# GR_Barillet.net
KiCad netlist of a schematic drawn in Altium Designer
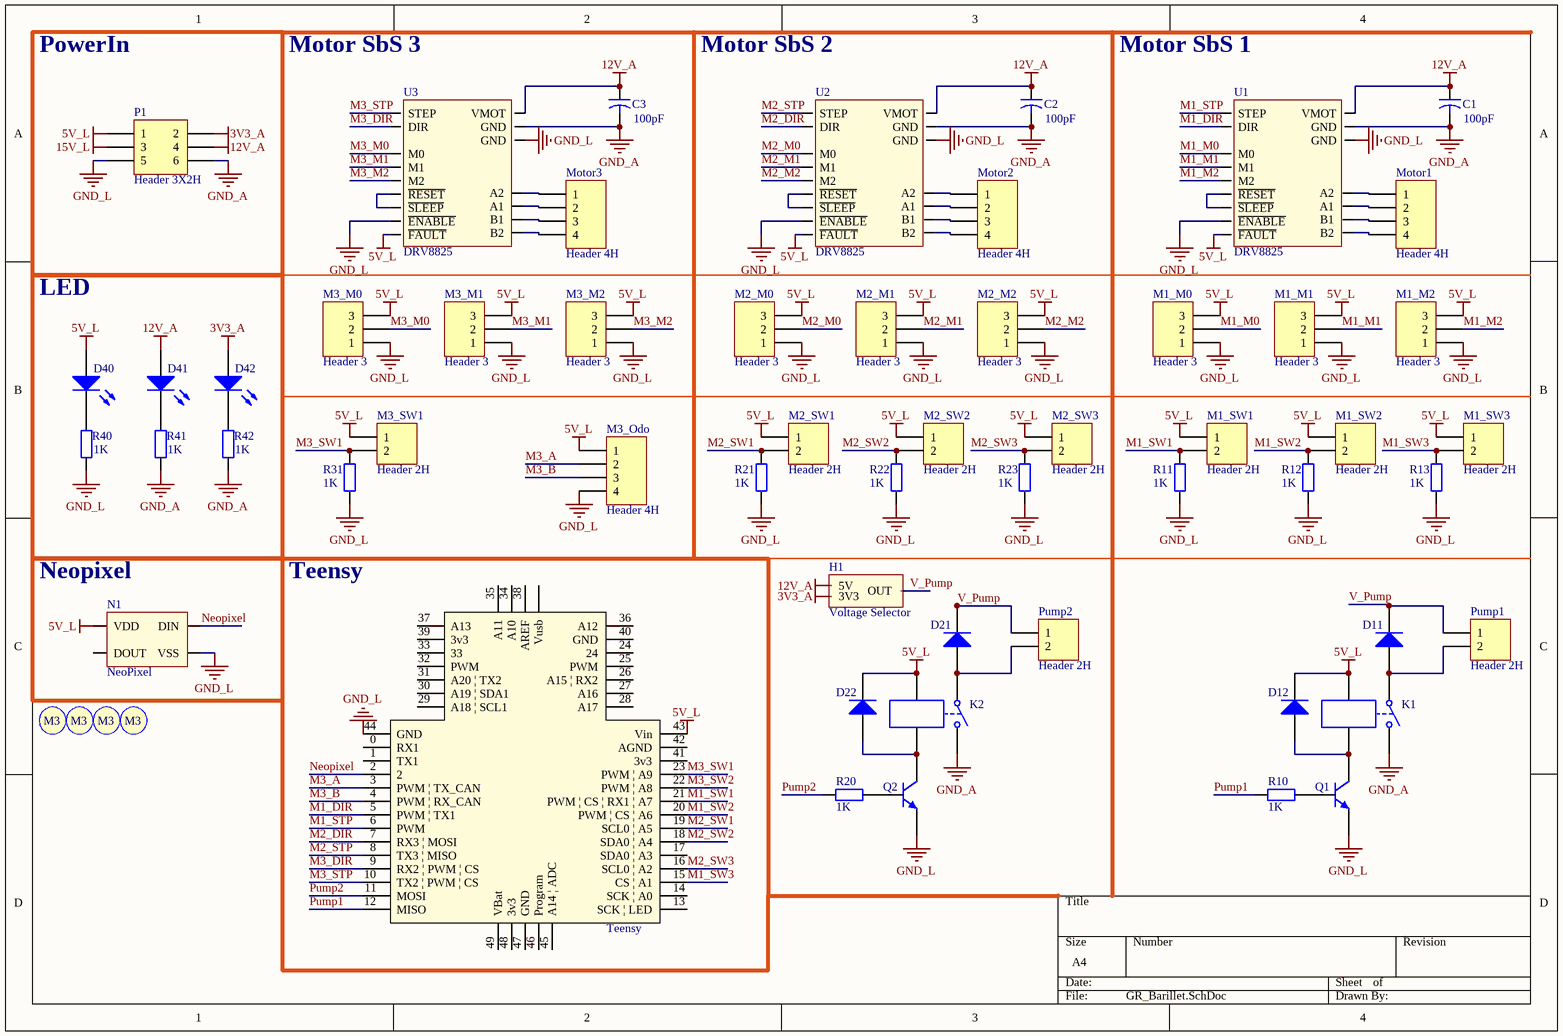
[diagram p0: GR_Barillet.SchDoc]

(export (version "E")
  (design (tool "Eeschema 10.0.6"))
  (components
    (comp (ref "C1")
      (value "100pF")
      (footprint "Condensateur")
      (description "Capacitor")
      (fields (field (name "Comment") "Cap2") (field (name "PUBLISHER") "Altium Limited"))
      (libsource (lib "Miscellaneous Devices") (part "Cap2"))
    )
    (comp (ref "C2")
      (value "100pF")
      (footprint "Condensateur")
      (description "Capacitor")
      (fields (field (name "Comment") "Cap2") (field (name "PUBLISHER") "Altium Limited"))
      (libsource (lib "Miscellaneous Devices") (part "Cap2"))
    )
    (comp (ref "C3")
      (value "100pF")
      (footprint "Condensateur")
      (description "Capacitor")
      (fields (field (name "Comment") "Cap2") (field (name "PUBLISHER") "Altium Limited"))
      (libsource (lib "Miscellaneous Devices") (part "Cap2"))
    )
    (comp (ref "D11")
      (value "Diode")
      (footprint "AXIAL-0.3")
      (description "Default Diode")
      (fields (field (name "PUBLISHER") "Altium Limited"))
      (libsource (lib "Miscellaneous Devices") (part "Diode"))
    )
    (comp (ref "D12")
      (value "Diode")
      (footprint "3.2X1.6X1.1")
      (description "Default Diode")
      (fields (field (name "PUBLISHER") "Altium Limited"))
      (libsource (lib "Miscellaneous Devices") (part "Diode"))
    )
    (comp (ref "D21")
      (value "Diode")
      (footprint "AXIAL-0.3")
      (description "Default Diode")
      (fields (field (name "PUBLISHER") "Altium Limited"))
      (libsource (lib "Miscellaneous Devices") (part "Diode"))
    )
    (comp (ref "D22")
      (value "Diode")
      (footprint "3.2X1.6X1.1")
      (description "Default Diode")
      (fields (field (name "PUBLISHER") "Altium Limited"))
      (libsource (lib "Miscellaneous Devices") (part "Diode"))
    )
    (comp (ref "D40")
      (value "LED0")
      (footprint "3.2X1.6X1.1")
      (description "Typical INFRARED GaAs LED")
      (fields (field (name "PUBLISHER") "Altium Limited"))
      (libsource (lib "Miscellaneous Devices") (part "LED0"))
    )
    (comp (ref "D41")
      (value "LED0")
      (footprint "3.2X1.6X1.1")
      (description "Typical INFRARED GaAs LED")
      (fields (field (name "PUBLISHER") "Altium Limited"))
      (libsource (lib "Miscellaneous Devices") (part "LED0"))
    )
    (comp (ref "D42")
      (value "LED0")
      (footprint "3.2X1.6X1.1")
      (description "Typical INFRARED GaAs LED")
      (fields (field (name "PUBLISHER") "Altium Limited"))
      (libsource (lib "Miscellaneous Devices") (part "LED0"))
    )
    (comp (ref "H1")
      (value "Voltage Selector")
      (footprint "Robot_2019:VOLTAGE SELECTOR")
      (description "Selection of voltage by soldering pads")
      (libsource (lib "Robot_2019") (part "Voltage Selector"))
    )
    (comp (ref "K1")
      (value "Relay-SPST")
      (footprint "Relay")
      (description "Single-Pole Single-Throw Relay")
      (fields (field (name "PUBLISHER") "Altium Limited"))
      (libsource (lib "Miscellaneous Devices") (part "Relay-SPST"))
    )
    (comp (ref "K2")
      (value "Relay-SPST")
      (footprint "Relay")
      (description "Single-Pole Single-Throw Relay")
      (fields (field (name "PUBLISHER") "Altium Limited"))
      (libsource (lib "Miscellaneous Devices") (part "Relay-SPST"))
    )
    (comp (ref "M1_M0")
      (value "Header 3")
      (footprint "HDR1X3")
      (description "Header, 3-Pin")
      (fields (field (name "PUBLISHER") "Altium Limited"))
      (libsource (lib "Miscellaneous Connectors") (part "Header 3"))
    )
    (comp (ref "M1_M1")
      (value "Header 3")
      (footprint "HDR1X3")
      (description "Header, 3-Pin")
      (fields (field (name "PUBLISHER") "Altium Limited"))
      (libsource (lib "Miscellaneous Connectors") (part "Header 3"))
    )
    (comp (ref "M1_M2")
      (value "Header 3")
      (footprint "HDR1X3")
      (description "Header, 3-Pin")
      (fields (field (name "PUBLISHER") "Altium Limited"))
      (libsource (lib "Miscellaneous Connectors") (part "Header 3"))
    )
    (comp (ref "M1_SW1")
      (value "Header 2H")
      (footprint "Molex SPOX 2x1H")
      (description "Header, 2-Pin, Right Angle")
      (fields (field (name "PUBLISHER") "Altium Limited"))
      (libsource (lib "Miscellaneous Connectors") (part "Header 2H"))
    )
    (comp (ref "M1_SW2")
      (value "Header 2H")
      (footprint "Molex SPOX 2x1H")
      (description "Header, 2-Pin, Right Angle")
      (fields (field (name "PUBLISHER") "Altium Limited"))
      (libsource (lib "Miscellaneous Connectors") (part "Header 2H"))
    )
    (comp (ref "M1_SW3")
      (value "Header 2H")
      (footprint "Molex SPOX 2x1H")
      (description "Header, 2-Pin, Right Angle")
      (fields (field (name "PUBLISHER") "Altium Limited"))
      (libsource (lib "Miscellaneous Connectors") (part "Header 2H"))
    )
    (comp (ref "M2_M0")
      (value "Header 3")
      (footprint "HDR1X3")
      (description "Header, 3-Pin")
      (fields (field (name "PUBLISHER") "Altium Limited"))
      (libsource (lib "Miscellaneous Connectors") (part "Header 3"))
    )
    (comp (ref "M2_M1")
      (value "Header 3")
      (footprint "HDR1X3")
      (description "Header, 3-Pin")
      (fields (field (name "PUBLISHER") "Altium Limited"))
      (libsource (lib "Miscellaneous Connectors") (part "Header 3"))
    )
    (comp (ref "M2_M2")
      (value "Header 3")
      (footprint "HDR1X3")
      (description "Header, 3-Pin")
      (fields (field (name "PUBLISHER") "Altium Limited"))
      (libsource (lib "Miscellaneous Connectors") (part "Header 3"))
    )
    (comp (ref "M2_SW1")
      (value "Header 2H")
      (footprint "Molex SPOX 2x1H")
      (description "Header, 2-Pin, Right Angle")
      (fields (field (name "PUBLISHER") "Altium Limited"))
      (libsource (lib "Miscellaneous Connectors") (part "Header 2H"))
    )
    (comp (ref "M2_SW2")
      (value "Header 2H")
      (footprint "Molex SPOX 2x1H")
      (description "Header, 2-Pin, Right Angle")
      (fields (field (name "PUBLISHER") "Altium Limited"))
      (libsource (lib "Miscellaneous Connectors") (part "Header 2H"))
    )
    (comp (ref "M2_SW3")
      (value "Header 2H")
      (footprint "Molex SPOX 2x1H")
      (description "Header, 2-Pin, Right Angle")
      (fields (field (name "PUBLISHER") "Altium Limited"))
      (libsource (lib "Miscellaneous Connectors") (part "Header 2H"))
    )
    (comp (ref "M3_M0")
      (value "Header 3")
      (footprint "HDR1X3")
      (description "Header, 3-Pin")
      (fields (field (name "PUBLISHER") "Altium Limited"))
      (libsource (lib "Miscellaneous Connectors") (part "Header 3"))
    )
    (comp (ref "M3_M1")
      (value "Header 3")
      (footprint "HDR1X3")
      (description "Header, 3-Pin")
      (fields (field (name "PUBLISHER") "Altium Limited"))
      (libsource (lib "Miscellaneous Connectors") (part "Header 3"))
    )
    (comp (ref "M3_M2")
      (value "Header 3")
      (footprint "HDR1X3")
      (description "Header, 3-Pin")
      (fields (field (name "PUBLISHER") "Altium Limited"))
      (libsource (lib "Miscellaneous Connectors") (part "Header 3"))
    )
    (comp (ref "M3_Odo")
      (value "Header 4H")
      (footprint "Molex SPOX 4x1H")
      (description "Header, 4-Pin, Right Angle")
      (fields (field (name "PUBLISHER") "Altium Limited"))
      (libsource (lib "Miscellaneous Connectors") (part "Header 4H"))
    )
    (comp (ref "M3_SW1")
      (value "Header 2H")
      (footprint "Molex SPOX 2x1H")
      (description "Header, 2-Pin, Right Angle")
      (fields (field (name "PUBLISHER") "Altium Limited"))
      (libsource (lib "Miscellaneous Connectors") (part "Header 2H"))
    )
    (comp (ref "Motor1")
      (value "Header 4H")
      (footprint "Molex SPOX 4x1H")
      (description "Header, 4-Pin, Right Angle")
      (fields (field (name "PUBLISHER") "Altium Limited"))
      (libsource (lib "Miscellaneous Connectors") (part "Header 4H"))
    )
    (comp (ref "Motor2")
      (value "Header 4H")
      (footprint "Molex SPOX 4x1H")
      (description "Header, 4-Pin, Right Angle")
      (fields (field (name "PUBLISHER") "Altium Limited"))
      (libsource (lib "Miscellaneous Connectors") (part "Header 4H"))
    )
    (comp (ref "Motor3")
      (value "Header 4H")
      (footprint "Molex SPOX 4x1H")
      (description "Header, 4-Pin, Right Angle")
      (fields (field (name "PUBLISHER") "Altium Limited"))
      (libsource (lib "Miscellaneous Connectors") (part "Header 4H"))
    )
    (comp (ref "N1")
      (value "NeoPixel")
      (footprint "Robot_2019:Neopixel")
      (libsource (lib "Robot_2019") (part "NeoPixel"))
    )
    (comp (ref "P1")
      (value "Header 3X2H")
      (footprint "MOLEX_MINIFITJR_3X2")
      (description "Header, 3-Pin, Dual row, Right Angle")
      (fields (field (name "PUBLISHER") "Altium Limited"))
      (libsource (lib "Miscellaneous Connectors") (part "Header 3X2H"))
    )
    (comp (ref "Pump1")
      (value "Header 2H")
      (footprint "Molex SPOX 2x1H")
      (description "Header, 2-Pin, Right Angle")
      (fields (field (name "PUBLISHER") "Altium Limited"))
      (libsource (lib "Miscellaneous Connectors") (part "Header 2H"))
    )
    (comp (ref "Pump2")
      (value "Header 2H")
      (footprint "Molex SPOX 2x1H")
      (description "Header, 2-Pin, Right Angle")
      (fields (field (name "PUBLISHER") "Altium Limited"))
      (libsource (lib "Miscellaneous Connectors") (part "Header 2H"))
    )
    (comp (ref "Q1")
      (value "NPN")
      (footprint "TO-226-AA")
      (description "NPN Bipolar Transistor")
      (fields (field (name "PUBLISHER") "Altium Limited"))
      (libsource (lib "Miscellaneous Devices") (part "NPN"))
    )
    (comp (ref "Q2")
      (value "NPN")
      (footprint "TO-226-AA")
      (description "NPN Bipolar Transistor")
      (fields (field (name "PUBLISHER") "Altium Limited"))
      (libsource (lib "Miscellaneous Devices") (part "NPN"))
    )
    (comp (ref "R10")
      (value "1K")
      (footprint "3.2X1.6X1.1")
      (description "Resistor")
      (fields (field (name "Comment") "Res2") (field (name "PUBLISHER") "Altium Limited"))
      (libsource (lib "") (part "Res2_1"))
    )
    (comp (ref "R11")
      (value "1K")
      (footprint "3.2X1.6X1.1")
      (description "Resistor")
      (fields (field (name "Comment") "Res1") (field (name "PUBLISHER") "Altium Limited"))
      (libsource (lib "Miscellaneous Devices") (part "Res2"))
    )
    (comp (ref "R12")
      (value "1K")
      (footprint "3.2X1.6X1.1")
      (description "Resistor")
      (fields (field (name "Comment") "Res1") (field (name "PUBLISHER") "Altium Limited"))
      (libsource (lib "Miscellaneous Devices") (part "Res2"))
    )
    (comp (ref "R13")
      (value "1K")
      (footprint "3.2X1.6X1.1")
      (description "Resistor")
      (fields (field (name "Comment") "Res1") (field (name "PUBLISHER") "Altium Limited"))
      (libsource (lib "Miscellaneous Devices") (part "Res2"))
    )
    (comp (ref "R20")
      (value "1K")
      (footprint "3.2X1.6X1.1")
      (description "Resistor")
      (fields (field (name "Comment") "Res2") (field (name "PUBLISHER") "Altium Limited"))
      (libsource (lib "") (part "Res2_1"))
    )
    (comp (ref "R21")
      (value "1K")
      (footprint "3.2X1.6X1.1")
      (description "Resistor")
      (fields (field (name "Comment") "Res1") (field (name "PUBLISHER") "Altium Limited"))
      (libsource (lib "Miscellaneous Devices") (part "Res2"))
    )
    (comp (ref "R22")
      (value "1K")
      (footprint "3.2X1.6X1.1")
      (description "Resistor")
      (fields (field (name "Comment") "Res1") (field (name "PUBLISHER") "Altium Limited"))
      (libsource (lib "Miscellaneous Devices") (part "Res2"))
    )
    (comp (ref "R23")
      (value "1K")
      (footprint "3.2X1.6X1.1")
      (description "Resistor")
      (fields (field (name "Comment") "Res1") (field (name "PUBLISHER") "Altium Limited"))
      (libsource (lib "Miscellaneous Devices") (part "Res2"))
    )
    (comp (ref "R31")
      (value "1K")
      (footprint "3.2X1.6X1.1")
      (description "Resistor")
      (fields (field (name "Comment") "Res1") (field (name "PUBLISHER") "Altium Limited"))
      (libsource (lib "Miscellaneous Devices") (part "Res2"))
    )
    (comp (ref "R40")
      (value "1K")
      (footprint "3.2X1.6X1.1")
      (description "Resistor")
      (fields (field (name "Comment") "Res2") (field (name "PUBLISHER") "Altium Limited"))
      (libsource (lib "Miscellaneous Devices") (part "Res2"))
    )
    (comp (ref "R41")
      (value "1K")
      (footprint "3.2X1.6X1.1")
      (description "Resistor")
      (fields (field (name "Comment") "Res2") (field (name "PUBLISHER") "Altium Limited"))
      (libsource (lib "Miscellaneous Devices") (part "Res2"))
    )
    (comp (ref "R42")
      (value "1K")
      (footprint "3.2X1.6X1.1")
      (description "Resistor")
      (fields (field (name "Comment") "Res2") (field (name "PUBLISHER") "Altium Limited"))
      (libsource (lib "Miscellaneous Devices") (part "Res2"))
    )
    (comp (ref "S1")
      (value "Screw M3")
      (footprint "Robot_2019:Screw M3")
      (libsource (lib "Robot_2019") (part "Screw M3"))
    )
    (comp (ref "S2")
      (value "Screw M3")
      (footprint "Robot_2019:Screw M3")
      (libsource (lib "Robot_2019") (part "Screw M3"))
    )
    (comp (ref "S3")
      (value "Screw M3")
      (footprint "Robot_2019:Screw M3")
      (libsource (lib "Robot_2019") (part "Screw M3"))
    )
    (comp (ref "S4")
      (value "Screw M3")
      (footprint "Robot_2019:Screw M3")
      (libsource (lib "Robot_2019") (part "Screw M3"))
    )
    (comp (ref "Teensy")
      (value "Teensy 3.2")
      (footprint "Robot_2019:teensy")
      (libsource (lib "Robot_2019") (part "teensy3.2"))
    )
    (comp (ref "U1")
      (value "DRV8825")
      (footprint "DRV8825")
      (description "Stepper Driver Module")
      (libsource (lib "Robot_2019") (part "DRV8825"))
    )
    (comp (ref "U2")
      (value "DRV8825")
      (footprint "DRV8825")
      (description "Stepper Driver Module")
      (libsource (lib "Robot_2019") (part "DRV8825"))
    )
    (comp (ref "U3")
      (value "DRV8825")
      (footprint "DRV8825")
      (description "Stepper Driver Module")
      (libsource (lib "Robot_2019") (part "DRV8825"))
    )
  )
  (nets
    (net (code "1") (name "/M1_DIR") (class "Default")
      (node (ref "Teensy") (pin "5") (pinfunction "PWM_¦_TX1_5") (pintype "passive"))
      (node (ref "U1") (pin "8") (pinfunction "DIR_8") (pintype "passive"))
    )
    (net (code "2") (name "/M1_M0") (class "Default")
      (node (ref "M1_M0") (pin "2") (pinfunction "2_2") (pintype "passive"))
      (node (ref "U1") (pin "2") (pinfunction "M0_2") (pintype "passive"))
    )
    (net (code "3") (name "/M1_M1") (class "Default")
      (node (ref "M1_M1") (pin "2") (pinfunction "2_2") (pintype "passive"))
      (node (ref "U1") (pin "3") (pinfunction "M1_3") (pintype "passive"))
    )
    (net (code "4") (name "/M1_M2") (class "Default")
      (node (ref "M1_M2") (pin "2") (pinfunction "2_2") (pintype "passive"))
      (node (ref "U1") (pin "4") (pinfunction "M2_4") (pintype "passive"))
    )
    (net (code "5") (name "/M1_STP") (class "Default")
      (node (ref "Teensy") (pin "6") (pinfunction "PWM_6") (pintype "passive"))
      (node (ref "U1") (pin "7") (pinfunction "STEP_7") (pintype "passive"))
    )
    (net (code "6") (name "/M1_SW1") (class "Default")
      (node (ref "M1_SW1") (pin "2") (pinfunction "2_2") (pintype "passive"))
      (node (ref "R11") (pin "2") (pinfunction "2_2") (pintype "passive"))
      (node (ref "Teensy") (pin "21") (pinfunction "PWM_¦_CS_¦_RX1_¦_A7_21") (pintype "passive"))
    )
    (net (code "7") (name "/M1_SW2") (class "Default")
      (node (ref "M1_SW2") (pin "2") (pinfunction "2_2") (pintype "passive"))
      (node (ref "R12") (pin "2") (pinfunction "2_2") (pintype "passive"))
      (node (ref "Teensy") (pin "20") (pinfunction "PWM_¦_CS_¦_A6_20") (pintype "passive"))
    )
    (net (code "8") (name "/M1_SW3") (class "Default")
      (node (ref "M1_SW3") (pin "2") (pinfunction "2_2") (pintype "passive"))
      (node (ref "R13") (pin "2") (pinfunction "2_2") (pintype "passive"))
      (node (ref "Teensy") (pin "15") (pinfunction "CS_¦_A1_15") (pintype "passive"))
    )
    (net (code "9") (name "/M2_DIR") (class "Default")
      (node (ref "Teensy") (pin "7") (pinfunction "RX3_¦_MOSI_7") (pintype "passive"))
      (node (ref "U2") (pin "8") (pinfunction "DIR_8") (pintype "passive"))
    )
    (net (code "10") (name "/M2_M0") (class "Default")
      (node (ref "M2_M0") (pin "2") (pinfunction "2_2") (pintype "passive"))
      (node (ref "U2") (pin "2") (pinfunction "M0_2") (pintype "passive"))
    )
    (net (code "11") (name "/M2_M1") (class "Default")
      (node (ref "M2_M1") (pin "2") (pinfunction "2_2") (pintype "passive"))
      (node (ref "U2") (pin "3") (pinfunction "M1_3") (pintype "passive"))
    )
    (net (code "12") (name "/M2_M2") (class "Default")
      (node (ref "M2_M2") (pin "2") (pinfunction "2_2") (pintype "passive"))
      (node (ref "U2") (pin "4") (pinfunction "M2_4") (pintype "passive"))
    )
    (net (code "13") (name "/M2_STP") (class "Default")
      (node (ref "Teensy") (pin "8") (pinfunction "TX3_¦_MISO_8") (pintype "passive"))
      (node (ref "U2") (pin "7") (pinfunction "STEP_7") (pintype "passive"))
    )
    (net (code "14") (name "/M2_SW1") (class "Default")
      (node (ref "M2_SW1") (pin "2") (pinfunction "2_2") (pintype "passive"))
      (node (ref "R21") (pin "2") (pinfunction "2_2") (pintype "passive"))
      (node (ref "Teensy") (pin "19") (pinfunction "SCL0_¦_A5_19") (pintype "passive"))
    )
    (net (code "15") (name "/M2_SW2") (class "Default")
      (node (ref "M2_SW2") (pin "2") (pinfunction "2_2") (pintype "passive"))
      (node (ref "R22") (pin "2") (pinfunction "2_2") (pintype "passive"))
      (node (ref "Teensy") (pin "18") (pinfunction "SDA0_¦_A4_18") (pintype "passive"))
    )
    (net (code "16") (name "/M2_SW3") (class "Default")
      (node (ref "M2_SW3") (pin "2") (pinfunction "2_2") (pintype "passive"))
      (node (ref "R23") (pin "2") (pinfunction "2_2") (pintype "passive"))
      (node (ref "Teensy") (pin "16") (pinfunction "SCL0_¦_A2_16") (pintype "passive"))
    )
    (net (code "17") (name "/M3_A") (class "Default")
      (node (ref "M3_Odo") (pin "2") (pinfunction "2_2") (pintype "passive"))
      (node (ref "Teensy") (pin "3") (pinfunction "PWM_¦_TX_CAN_3") (pintype "passive"))
    )
    (net (code "18") (name "/M3_B") (class "Default")
      (node (ref "M3_Odo") (pin "3") (pinfunction "3_3") (pintype "passive"))
      (node (ref "Teensy") (pin "4") (pinfunction "PWM_¦_RX_CAN_4") (pintype "passive"))
    )
    (net (code "19") (name "/M3_DIR") (class "Default")
      (node (ref "Teensy") (pin "9") (pinfunction "RX2_¦_PWM_¦_CS_9") (pintype "passive"))
      (node (ref "U3") (pin "8") (pinfunction "DIR_8") (pintype "passive"))
    )
    (net (code "20") (name "/M3_M0") (class "Default")
      (node (ref "M3_M0") (pin "2") (pinfunction "2_2") (pintype "passive"))
      (node (ref "U3") (pin "2") (pinfunction "M0_2") (pintype "passive"))
    )
    (net (code "21") (name "/M3_M1") (class "Default")
      (node (ref "M3_M1") (pin "2") (pinfunction "2_2") (pintype "passive"))
      (node (ref "U3") (pin "3") (pinfunction "M1_3") (pintype "passive"))
    )
    (net (code "22") (name "/M3_M2") (class "Default")
      (node (ref "M3_M2") (pin "2") (pinfunction "2_2") (pintype "passive"))
      (node (ref "U3") (pin "4") (pinfunction "M2_4") (pintype "passive"))
    )
    (net (code "23") (name "/M3_STP") (class "Default")
      (node (ref "Teensy") (pin "10") (pinfunction "TX2_¦_PWM_¦_CS_10") (pintype "passive"))
      (node (ref "U3") (pin "7") (pinfunction "STEP_7") (pintype "passive"))
    )
    (net (code "24") (name "/M3_SW1") (class "Default")
      (node (ref "M3_SW1") (pin "2") (pinfunction "2_2") (pintype "passive"))
      (node (ref "R31") (pin "2") (pinfunction "2_2") (pintype "passive"))
      (node (ref "Teensy") (pin "23") (pinfunction "PWM_¦_A9_23") (pintype "passive"))
    )
    (net (code "25") (name "/M3_SW2") (class "Default")
      (node (ref "Teensy") (pin "22") (pinfunction "PWM_¦_A8_22") (pintype "passive"))
    )
    (net (code "26") (name "/Neopixel") (class "Default")
      (node (ref "N1") (pin "3") (pinfunction "DIN_3") (pintype "passive"))
      (node (ref "Teensy") (pin "2") (pinfunction "2_2") (pintype "passive"))
    )
    (net (code "27") (name "/Pump1") (class "Default")
      (node (ref "R10") (pin "1") (pinfunction "1_1") (pintype "passive"))
      (node (ref "Teensy") (pin "12") (pinfunction "MISO_12") (pintype "passive"))
    )
    (net (code "28") (name "/Pump2") (class "Default")
      (node (ref "R20") (pin "1") (pinfunction "1_1") (pintype "passive"))
      (node (ref "Teensy") (pin "11") (pinfunction "MOSI_11") (pintype "passive"))
    )
    (net (code "29") (name "/V_Pump") (class "Default")
      (node (ref "D11") (pin "2") (pinfunction "K_2") (pintype "passive"))
      (node (ref "D21") (pin "2") (pinfunction "K_2") (pintype "passive"))
      (node (ref "H1") (pin "3") (pinfunction "OUT_3") (pintype "passive"))
      (node (ref "Pump1") (pin "1") (pinfunction "1_1") (pintype "passive"))
      (node (ref "Pump2") (pin "1") (pinfunction "1_1") (pintype "passive"))
    )
    (net (code "30") (name "3V3_A") (class "Default")
      (node (ref "D42") (pin "1") (pinfunction "A_1") (pintype "passive"))
      (node (ref "H1") (pin "2") (pinfunction "3V3_2") (pintype "passive"))
      (node (ref "P1") (pin "2") (pinfunction "2_2") (pintype "passive"))
    )
    (net (code "31") (name "5V_L") (class "Default")
      (node (ref "D12") (pin "2") (pinfunction "K_2") (pintype "passive"))
      (node (ref "D22") (pin "2") (pinfunction "K_2") (pintype "passive"))
      (node (ref "D40") (pin "1") (pinfunction "A_1") (pintype "passive"))
      (node (ref "K1") (pin "3") (pinfunction "3_3") (pintype "passive"))
      (node (ref "K2") (pin "3") (pinfunction "3_3") (pintype "passive"))
      (node (ref "M1_M0") (pin "3") (pinfunction "3_3") (pintype "passive"))
      (node (ref "M1_M1") (pin "3") (pinfunction "3_3") (pintype "passive"))
      (node (ref "M1_M2") (pin "3") (pinfunction "3_3") (pintype "passive"))
      (node (ref "M1_SW1") (pin "1") (pinfunction "1_1") (pintype "passive"))
      (node (ref "M1_SW2") (pin "1") (pinfunction "1_1") (pintype "passive"))
      (node (ref "M1_SW3") (pin "1") (pinfunction "1_1") (pintype "passive"))
      (node (ref "M2_M0") (pin "3") (pinfunction "3_3") (pintype "passive"))
      (node (ref "M2_M1") (pin "3") (pinfunction "3_3") (pintype "passive"))
      (node (ref "M2_M2") (pin "3") (pinfunction "3_3") (pintype "passive"))
      (node (ref "M2_SW1") (pin "1") (pinfunction "1_1") (pintype "passive"))
      (node (ref "M2_SW2") (pin "1") (pinfunction "1_1") (pintype "passive"))
      (node (ref "M2_SW3") (pin "1") (pinfunction "1_1") (pintype "passive"))
      (node (ref "M3_M0") (pin "3") (pinfunction "3_3") (pintype "passive"))
      (node (ref "M3_M1") (pin "3") (pinfunction "3_3") (pintype "passive"))
      (node (ref "M3_M2") (pin "3") (pinfunction "3_3") (pintype "passive"))
      (node (ref "M3_Odo") (pin "1") (pinfunction "1_1") (pintype "passive"))
      (node (ref "M3_SW1") (pin "1") (pinfunction "1_1") (pintype "passive"))
      (node (ref "N1") (pin "4") (pinfunction "VDD_4") (pintype "passive"))
      (node (ref "P1") (pin "1") (pinfunction "1_1") (pintype "passive"))
      (node (ref "Teensy") (pin "43") (pinfunction "Vin_43") (pintype "passive"))
      (node (ref "U1") (pin "10") (pinfunction "~{FAULT}_10") (pintype "passive"))
      (node (ref "U2") (pin "10") (pinfunction "~{FAULT}_10") (pintype "passive"))
      (node (ref "U3") (pin "10") (pinfunction "~{FAULT}_10") (pintype "passive"))
    )
    (net (code "32") (name "12V_A") (class "Default")
      (node (ref "C1") (pin "1") (pinfunction "1_1") (pintype "passive"))
      (node (ref "C2") (pin "1") (pinfunction "1_1") (pintype "passive"))
      (node (ref "C3") (pin "1") (pinfunction "1_1") (pintype "passive"))
      (node (ref "D41") (pin "1") (pinfunction "A_1") (pintype "passive"))
      (node (ref "H1") (pin "1") (pinfunction "5V_1") (pintype "passive"))
      (node (ref "P1") (pin "4") (pinfunction "4_4") (pintype "passive"))
      (node (ref "U1") (pin "16") (pinfunction "VMOT_16") (pintype "passive"))
      (node (ref "U2") (pin "16") (pinfunction "VMOT_16") (pintype "passive"))
      (node (ref "U3") (pin "16") (pinfunction "VMOT_16") (pintype "passive"))
    )
    (net (code "33") (name "15V_L") (class "Default")
      (node (ref "P1") (pin "3") (pinfunction "3_3") (pintype "passive"))
    )
    (net (code "34") (name "GND_A") (class "Default")
      (node (ref "C1") (pin "2") (pinfunction "2_2") (pintype "passive"))
      (node (ref "C2") (pin "2") (pinfunction "2_2") (pintype "passive"))
      (node (ref "C3") (pin "2") (pinfunction "2_2") (pintype "passive"))
      (node (ref "K1") (pin "2") (pinfunction "2_2") (pintype "passive"))
      (node (ref "K2") (pin "2") (pinfunction "2_2") (pintype "passive"))
      (node (ref "P1") (pin "6") (pinfunction "6_6") (pintype "passive"))
      (node (ref "R41") (pin "1") (pinfunction "1_1") (pintype "passive"))
      (node (ref "R42") (pin "1") (pinfunction "1_1") (pintype "passive"))
      (node (ref "U1") (pin "15") (pinfunction "GND_15") (pintype "passive"))
      (node (ref "U2") (pin "15") (pinfunction "GND_15") (pintype "passive"))
      (node (ref "U3") (pin "15") (pinfunction "GND_15") (pintype "passive"))
    )
    (net (code "35") (name "GND_L") (class "Default")
      (node (ref "M1_M0") (pin "1") (pinfunction "1_1") (pintype "passive"))
      (node (ref "M1_M1") (pin "1") (pinfunction "1_1") (pintype "passive"))
      (node (ref "M1_M2") (pin "1") (pinfunction "1_1") (pintype "passive"))
      (node (ref "M2_M0") (pin "1") (pinfunction "1_1") (pintype "passive"))
      (node (ref "M2_M1") (pin "1") (pinfunction "1_1") (pintype "passive"))
      (node (ref "M2_M2") (pin "1") (pinfunction "1_1") (pintype "passive"))
      (node (ref "M3_M0") (pin "1") (pinfunction "1_1") (pintype "passive"))
      (node (ref "M3_M1") (pin "1") (pinfunction "1_1") (pintype "passive"))
      (node (ref "M3_M2") (pin "1") (pinfunction "1_1") (pintype "passive"))
      (node (ref "M3_Odo") (pin "4") (pinfunction "4_4") (pintype "passive"))
      (node (ref "N1") (pin "2") (pinfunction "VSS_2") (pintype "passive"))
      (node (ref "P1") (pin "5") (pinfunction "5_5") (pintype "passive"))
      (node (ref "Q1") (pin "3") (pinfunction "E_3") (pintype "passive"))
      (node (ref "Q2") (pin "3") (pinfunction "E_3") (pintype "passive"))
      (node (ref "R11") (pin "1") (pinfunction "1_1") (pintype "passive"))
      (node (ref "R12") (pin "1") (pinfunction "1_1") (pintype "passive"))
      (node (ref "R13") (pin "1") (pinfunction "1_1") (pintype "passive"))
      (node (ref "R21") (pin "1") (pinfunction "1_1") (pintype "passive"))
      (node (ref "R22") (pin "1") (pinfunction "1_1") (pintype "passive"))
      (node (ref "R23") (pin "1") (pinfunction "1_1") (pintype "passive"))
      (node (ref "R31") (pin "1") (pinfunction "1_1") (pintype "passive"))
      (node (ref "R40") (pin "1") (pinfunction "1_1") (pintype "passive"))
      (node (ref "Teensy") (pin "44") (pinfunction "GND_44") (pintype "passive"))
      (node (ref "U1") (pin "1") (pinfunction "~{ENABLE}_1") (pintype "passive"))
      (node (ref "U1") (pin "9") (pinfunction "GND_9") (pintype "passive"))
      (node (ref "U2") (pin "1") (pinfunction "~{ENABLE}_1") (pintype "passive"))
      (node (ref "U2") (pin "9") (pinfunction "GND_9") (pintype "passive"))
      (node (ref "U3") (pin "1") (pinfunction "~{ENABLE}_1") (pintype "passive"))
      (node (ref "U3") (pin "9") (pinfunction "GND_9") (pintype "passive"))
    )
    (net (code "36") (name "Net-(D11-A)") (class "Default")
      (node (ref "D11") (pin "1") (pinfunction "A_1") (pintype "passive"))
      (node (ref "K1") (pin "1") (pinfunction "1_1") (pintype "passive"))
      (node (ref "Pump1") (pin "2") (pinfunction "2_2") (pintype "passive"))
    )
    (net (code "37") (name "Net-(D12-A)") (class "Default")
      (node (ref "D12") (pin "1") (pinfunction "A_1") (pintype "passive"))
      (node (ref "K1") (pin "4") (pinfunction "4_4") (pintype "passive"))
      (node (ref "Q1") (pin "1") (pinfunction "C_1") (pintype "passive"))
    )
    (net (code "38") (name "Net-(D21-A)") (class "Default")
      (node (ref "D21") (pin "1") (pinfunction "A_1") (pintype "passive"))
      (node (ref "K2") (pin "1") (pinfunction "1_1") (pintype "passive"))
      (node (ref "Pump2") (pin "2") (pinfunction "2_2") (pintype "passive"))
    )
    (net (code "39") (name "Net-(D22-A)") (class "Default")
      (node (ref "D22") (pin "1") (pinfunction "A_1") (pintype "passive"))
      (node (ref "K2") (pin "4") (pinfunction "4_4") (pintype "passive"))
      (node (ref "Q2") (pin "1") (pinfunction "C_1") (pintype "passive"))
    )
    (net (code "40") (name "Net-(D40-K)") (class "Default")
      (node (ref "D40") (pin "2") (pinfunction "K_2") (pintype "passive"))
      (node (ref "R40") (pin "2") (pinfunction "2_2") (pintype "passive"))
    )
    (net (code "41") (name "Net-(D41-K)") (class "Default")
      (node (ref "D41") (pin "2") (pinfunction "K_2") (pintype "passive"))
      (node (ref "R41") (pin "2") (pinfunction "2_2") (pintype "passive"))
    )
    (net (code "42") (name "Net-(D42-K)") (class "Default")
      (node (ref "D42") (pin "2") (pinfunction "K_2") (pintype "passive"))
      (node (ref "R42") (pin "2") (pinfunction "2_2") (pintype "passive"))
    )
    (net (code "43") (name "Net-(Q1-B)") (class "Default")
      (node (ref "Q1") (pin "2") (pinfunction "B_2") (pintype "passive"))
      (node (ref "R10") (pin "2") (pinfunction "2_2") (pintype "passive"))
    )
    (net (code "44") (name "Net-(Q2-B)") (class "Default")
      (node (ref "Q2") (pin "2") (pinfunction "B_2") (pintype "passive"))
      (node (ref "R20") (pin "2") (pinfunction "2_2") (pintype "passive"))
    )
    (net (code "45") (name "Net-(U1-A1)") (class "Default")
      (node (ref "Motor1") (pin "2") (pinfunction "2_2") (pintype "passive"))
      (node (ref "U1") (pin "12") (pinfunction "A1_12") (pintype "passive"))
    )
    (net (code "46") (name "Net-(U1-A2)") (class "Default")
      (node (ref "Motor1") (pin "1") (pinfunction "1_1") (pintype "passive"))
      (node (ref "U1") (pin "11") (pinfunction "A2_11") (pintype "passive"))
    )
    (net (code "47") (name "Net-(U1-B1)") (class "Default")
      (node (ref "Motor1") (pin "3") (pinfunction "3_3") (pintype "passive"))
      (node (ref "U1") (pin "13") (pinfunction "B1_13") (pintype "passive"))
    )
    (net (code "48") (name "Net-(U1-B2)") (class "Default")
      (node (ref "Motor1") (pin "4") (pinfunction "4_4") (pintype "passive"))
      (node (ref "U1") (pin "14") (pinfunction "B2_14") (pintype "passive"))
    )
    (net (code "49") (name "Net-(U1-~{RESET})") (class "Default")
      (node (ref "U1") (pin "5") (pinfunction "~{RESET}_5") (pintype "passive"))
      (node (ref "U1") (pin "6") (pinfunction "~{SLEEP}_6") (pintype "passive"))
    )
    (net (code "50") (name "Net-(U2-A1)") (class "Default")
      (node (ref "Motor2") (pin "2") (pinfunction "2_2") (pintype "passive"))
      (node (ref "U2") (pin "12") (pinfunction "A1_12") (pintype "passive"))
    )
    (net (code "51") (name "Net-(U2-A2)") (class "Default")
      (node (ref "Motor2") (pin "1") (pinfunction "1_1") (pintype "passive"))
      (node (ref "U2") (pin "11") (pinfunction "A2_11") (pintype "passive"))
    )
    (net (code "52") (name "Net-(U2-B1)") (class "Default")
      (node (ref "Motor2") (pin "3") (pinfunction "3_3") (pintype "passive"))
      (node (ref "U2") (pin "13") (pinfunction "B1_13") (pintype "passive"))
    )
    (net (code "53") (name "Net-(U2-B2)") (class "Default")
      (node (ref "Motor2") (pin "4") (pinfunction "4_4") (pintype "passive"))
      (node (ref "U2") (pin "14") (pinfunction "B2_14") (pintype "passive"))
    )
    (net (code "54") (name "Net-(U2-~{RESET})") (class "Default")
      (node (ref "U2") (pin "5") (pinfunction "~{RESET}_5") (pintype "passive"))
      (node (ref "U2") (pin "6") (pinfunction "~{SLEEP}_6") (pintype "passive"))
    )
    (net (code "55") (name "Net-(U3-A1)") (class "Default")
      (node (ref "Motor3") (pin "2") (pinfunction "2_2") (pintype "passive"))
      (node (ref "U3") (pin "12") (pinfunction "A1_12") (pintype "passive"))
    )
    (net (code "56") (name "Net-(U3-A2)") (class "Default")
      (node (ref "Motor3") (pin "1") (pinfunction "1_1") (pintype "passive"))
      (node (ref "U3") (pin "11") (pinfunction "A2_11") (pintype "passive"))
    )
    (net (code "57") (name "Net-(U3-B1)") (class "Default")
      (node (ref "Motor3") (pin "3") (pinfunction "3_3") (pintype "passive"))
      (node (ref "U3") (pin "13") (pinfunction "B1_13") (pintype "passive"))
    )
    (net (code "58") (name "Net-(U3-B2)") (class "Default")
      (node (ref "Motor3") (pin "4") (pinfunction "4_4") (pintype "passive"))
      (node (ref "U3") (pin "14") (pinfunction "B2_14") (pintype "passive"))
    )
    (net (code "59") (name "Net-(U3-~{RESET})") (class "Default")
      (node (ref "U3") (pin "5") (pinfunction "~{RESET}_5") (pintype "passive"))
      (node (ref "U3") (pin "6") (pinfunction "~{SLEEP}_6") (pintype "passive"))
    )
    (net (code "60") (name "unconnected-(N1-DOUT-Pad1)") (class "Default")
      (node (ref "N1") (pin "1") (pinfunction "DOUT_1") (pintype "passive"))
    )
    (net (code "61") (name "unconnected-(Teensy-3v3-Pad39)") (class "Default")
      (node (ref "Teensy") (pin "39") (pinfunction "3v3_39") (pintype "passive"))
    )
    (net (code "62") (name "unconnected-(Teensy-3v3-Pad41)") (class "Default")
      (node (ref "Teensy") (pin "41") (pinfunction "3v3_41") (pintype "passive"))
    )
    (net (code "63") (name "unconnected-(Teensy-3v3-Pad48)") (class "Default")
      (node (ref "Teensy") (pin "48") (pinfunction "3v3_48") (pintype "passive"))
    )
    (net (code "64") (name "unconnected-(Teensy-A10-Pad34)") (class "Default")
      (node (ref "Teensy") (pin "34") (pinfunction "A10_34") (pintype "passive"))
    )
    (net (code "65") (name "unconnected-(Teensy-A11-Pad35)") (class "Default")
      (node (ref "Teensy") (pin "35") (pinfunction "A11_35") (pintype "passive"))
    )
    (net (code "66") (name "unconnected-(Teensy-A12-Pad36)") (class "Default")
      (node (ref "Teensy") (pin "36") (pinfunction "A12_36") (pintype "passive"))
    )
    (net (code "67") (name "unconnected-(Teensy-A13-Pad37)") (class "Default")
      (node (ref "Teensy") (pin "37") (pinfunction "A13_37") (pintype "passive"))
    )
    (net (code "68") (name "unconnected-(Teensy-A14_¦_ADC-Pad45)") (class "Default")
      (node (ref "Teensy") (pin "45") (pinfunction "A14_¦_ADC_45") (pintype "passive"))
    )
    (net (code "69") (name "unconnected-(Teensy-A15_¦_RX2-Pad26)") (class "Default")
      (node (ref "Teensy") (pin "26") (pinfunction "A15_¦_RX2_26") (pintype "passive"))
    )
    (net (code "70") (name "unconnected-(Teensy-A16-Pad27)") (class "Default")
      (node (ref "Teensy") (pin "27") (pinfunction "A16_27") (pintype "passive"))
    )
    (net (code "71") (name "unconnected-(Teensy-A17-Pad28)") (class "Default")
      (node (ref "Teensy") (pin "28") (pinfunction "A17_28") (pintype "passive"))
    )
    (net (code "72") (name "unconnected-(Teensy-A18_¦_SCL1-Pad29)") (class "Default")
      (node (ref "Teensy") (pin "29") (pinfunction "A18_¦_SCL1_29") (pintype "passive"))
    )
    (net (code "73") (name "unconnected-(Teensy-A19_¦_SDA1-Pad30)") (class "Default")
      (node (ref "Teensy") (pin "30") (pinfunction "A19_¦_SDA1_30") (pintype "passive"))
    )
    (net (code "74") (name "unconnected-(Teensy-A20_¦_TX2-Pad31)") (class "Default")
      (node (ref "Teensy") (pin "31") (pinfunction "A20_¦_TX2_31") (pintype "passive"))
    )
    (net (code "75") (name "unconnected-(Teensy-AGND-Pad42)") (class "Default")
      (node (ref "Teensy") (pin "42") (pinfunction "AGND_42") (pintype "passive"))
    )
    (net (code "76") (name "unconnected-(Teensy-AREF-Pad38)") (class "Default")
      (node (ref "Teensy") (pin "38") (pinfunction "AREF_38") (pintype "passive"))
    )
    (net (code "77") (name "unconnected-(Teensy-GND-Pad40)") (class "Default")
      (node (ref "Teensy") (pin "40") (pinfunction "GND_40") (pintype "passive"))
    )
    (net (code "78") (name "unconnected-(Teensy-GND-Pad47)") (class "Default")
      (node (ref "Teensy") (pin "47") (pinfunction "GND_47") (pintype "passive"))
    )
    (net (code "79") (name "unconnected-(Teensy-PWM-Pad25)") (class "Default")
      (node (ref "Teensy") (pin "25") (pinfunction "PWM_25") (pintype "passive"))
    )
    (net (code "80") (name "unconnected-(Teensy-PWM-Pad32)") (class "Default")
      (node (ref "Teensy") (pin "32") (pinfunction "PWM_32") (pintype "passive"))
    )
    (net (code "81") (name "unconnected-(Teensy-Pad24)") (class "Default")
      (node (ref "Teensy") (pin "24") (pinfunction "24_24") (pintype "passive"))
    )
    (net (code "82") (name "unconnected-(Teensy-Pad33)") (class "Default")
      (node (ref "Teensy") (pin "33") (pinfunction "33_33") (pintype "passive"))
    )
    (net (code "83") (name "unconnected-(Teensy-Program-Pad46)") (class "Default")
      (node (ref "Teensy") (pin "46") (pinfunction "Program_46") (pintype "passive"))
    )
    (net (code "84") (name "unconnected-(Teensy-RX1-Pad0)") (class "Default")
      (node (ref "Teensy") (pin "0") (pinfunction "RX1_0") (pintype "passive"))
    )
    (net (code "85") (name "unconnected-(Teensy-SCK_¦_A0-Pad14)") (class "Default")
      (node (ref "Teensy") (pin "14") (pinfunction "SCK_¦_A0_14") (pintype "passive"))
    )
    (net (code "86") (name "unconnected-(Teensy-SCK_¦_LED-Pad13)") (class "Default")
      (node (ref "Teensy") (pin "13") (pinfunction "SCK_¦_LED_13") (pintype "passive"))
    )
    (net (code "87") (name "unconnected-(Teensy-SDA0_¦_A3-Pad17)") (class "Default")
      (node (ref "Teensy") (pin "17") (pinfunction "SDA0_¦_A3_17") (pintype "passive"))
    )
    (net (code "88") (name "unconnected-(Teensy-TX1-Pad1)") (class "Default")
      (node (ref "Teensy") (pin "1") (pinfunction "TX1_1") (pintype "passive"))
    )
    (net (code "89") (name "unconnected-(Teensy-VBat-Pad49)") (class "Default")
      (node (ref "Teensy") (pin "49") (pinfunction "VBat_49") (pintype "passive"))
    )
    (net (code "90") (name "unconnected-(Teensy-Vusb-Pad50)") (class "Default")
      (node (ref "Teensy") (pin "50") (pinfunction "Vusb_50") (pintype "passive"))
    )
  )
)
